# attiny_sensor2.net
KiCad netlist of a schematic drawn in EAGLE
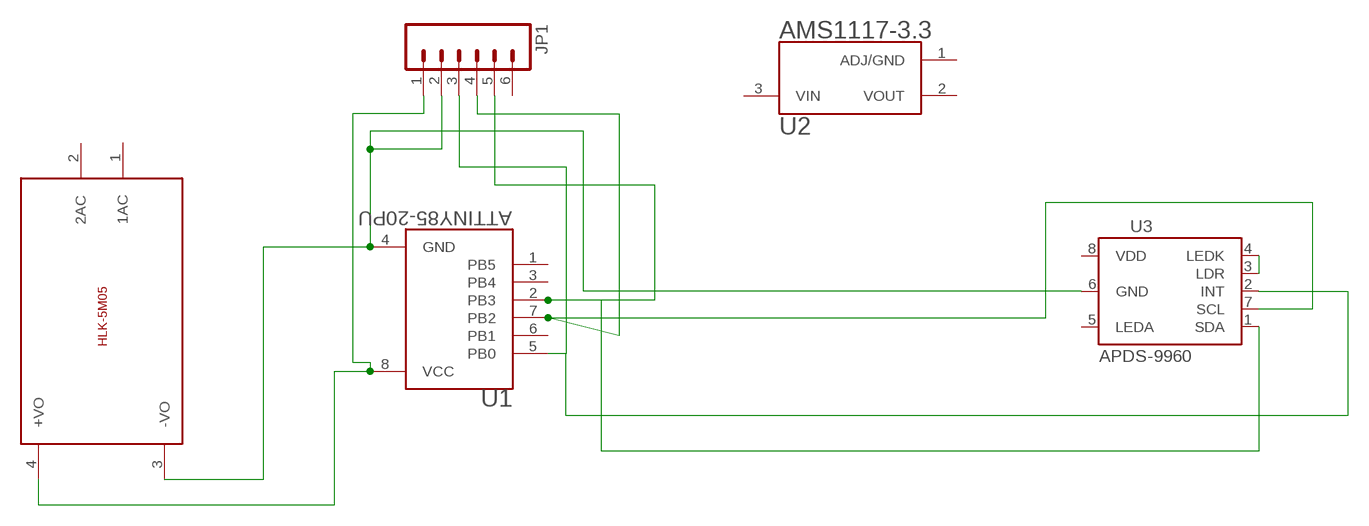
[diagram p0: schematic, sheet 1]

(export (version "E")
  (design (tool "Eeschema 10.0.6"))
  (components
    (comp (ref "JP1")
      (value "M06SIP")
      (footprint "eagle-import:1X06")
      (libsource (lib "eagle-import") (part "M06SIP"))
    )
    (comp (ref "U$1")
      (value "5VDC/5W")
      (footprint "eagle-import:HLK-5M05")
      (libsource (lib "eagle-import") (part "HLK-5M05"))
    )
    (comp (ref "U1")
      (value "ATTINY85-20PU")
      (footprint "eagle-import:DIP762W46P254L927H533Q8B")
      (fields (field (name "MF") "Microchip Technology"))
      (libsource (lib "eagle-import") (part "ATTINY85-20PU"))
    )
    (comp (ref "U2")
      (value "AMS1117-3.3")
      (footprint "eagle-import:SOT229P700X180-4N")
      (fields (field (name "MF") "Advanced Monolithic Systems"))
      (libsource (lib "eagle-import") (part "AMS1117-3.3"))
    )
    (comp (ref "U3")
      (value "APDS-9960")
      (footprint "eagle-import:APDS-9960")
      (libsource (lib "eagle-import") (part "APDS-9960"))
    )
  )
  (nets
    (net (code "1") (name "/ADJ{slash}GND") (class "Default")
      (node (ref "U2") (pin "1") (pinfunction "ADJ/GND_1") (pintype "power_in"))
    )
    (net (code "2") (name "Net-(U$1-+VO)") (class "Default")
      (node (ref "JP1") (pin "1") (pinfunction "1_1") (pintype "passive"))
      (node (ref "U$1") (pin "4") (pinfunction "+VO_4") (pintype "bidirectional"))
      (node (ref "U1") (pin "8") (pinfunction "VCC_8") (pintype "power_in"))
    )
    (net (code "3") (name "Net-(U$1--VO)") (class "Default")
      (node (ref "JP1") (pin "2") (pinfunction "2_2") (pintype "passive"))
      (node (ref "U$1") (pin "3") (pinfunction "-VO_3") (pintype "bidirectional"))
      (node (ref "U1") (pin "4") (pinfunction "GND_4") (pintype "power_in"))
      (node (ref "U3") (pin "6") (pinfunction "GND_6") (pintype "bidirectional"))
    )
    (net (code "4") (name "Net-(U1-PB0)") (class "Default")
      (node (ref "JP1") (pin "3") (pinfunction "3_3") (pintype "passive"))
      (node (ref "U1") (pin "5") (pinfunction "PB0_5") (pintype "bidirectional"))
      (node (ref "U3") (pin "2") (pinfunction "INT_2") (pintype "bidirectional"))
    )
    (net (code "5") (name "Net-(U1-PB2)") (class "Default")
      (node (ref "JP1") (pin "4") (pinfunction "4_4") (pintype "passive"))
      (node (ref "U1") (pin "7") (pinfunction "PB2_7") (pintype "bidirectional"))
      (node (ref "U3") (pin "7") (pinfunction "SCL_7") (pintype "bidirectional"))
    )
    (net (code "6") (name "Net-(U1-PB3)") (class "Default")
      (node (ref "JP1") (pin "5") (pinfunction "5_5") (pintype "passive"))
      (node (ref "U1") (pin "2") (pinfunction "PB3_2") (pintype "bidirectional"))
      (node (ref "U3") (pin "1") (pinfunction "SDA_1") (pintype "bidirectional"))
    )
    (net (code "7") (name "Net-(U3-LDR)") (class "Default")
      (node (ref "U3") (pin "3") (pinfunction "LDR_3") (pintype "bidirectional"))
      (node (ref "U3") (pin "4") (pinfunction "LEDK_4") (pintype "bidirectional"))
    )
    (net (code "8") (name "unconnected-(JP1-Pad6)") (class "Default")
      (node (ref "JP1") (pin "6") (pinfunction "6_6") (pintype "passive"))
    )
    (net (code "9") (name "unconnected-(U$1-1AC-Pad1)") (class "Default")
      (node (ref "U$1") (pin "1") (pinfunction "1AC_1") (pintype "bidirectional"))
    )
    (net (code "10") (name "unconnected-(U$1-2AC-Pad2)") (class "Default")
      (node (ref "U$1") (pin "2") (pinfunction "2AC_2") (pintype "bidirectional"))
    )
    (net (code "11") (name "unconnected-(U1-PB1-Pad6)") (class "Default")
      (node (ref "U1") (pin "6") (pinfunction "PB1_6") (pintype "bidirectional"))
    )
    (net (code "12") (name "unconnected-(U1-PB4-Pad3)") (class "Default")
      (node (ref "U1") (pin "3") (pinfunction "PB4_3") (pintype "bidirectional"))
    )
    (net (code "13") (name "unconnected-(U1-PB5-Pad1)") (class "Default")
      (node (ref "U1") (pin "1") (pinfunction "PB5_1") (pintype "bidirectional"))
    )
    (net (code "14") (name "unconnected-(U2-VIN-Pad3)") (class "Default")
      (node (ref "U2") (pin "3") (pinfunction "VIN_3") (pintype "input"))
    )
    (net (code "15") (name "unconnected-(U2-VOUT-Pad2)") (class "Default")
      (node (ref "U2") (pin "2") (pinfunction "VOUT_2") (pintype "output"))
    )
    (net (code "16") (name "unconnected-(U3-LEDA-Pad5)") (class "Default")
      (node (ref "U3") (pin "5") (pinfunction "LEDA_5") (pintype "bidirectional"))
    )
    (net (code "17") (name "unconnected-(U3-VDD-Pad8)") (class "Default")
      (node (ref "U3") (pin "8") (pinfunction "VDD_8") (pintype "bidirectional"))
    )
  )
)
